# 01_MAIN.net
KiCad netlist of a schematic drawn in Altium Designer
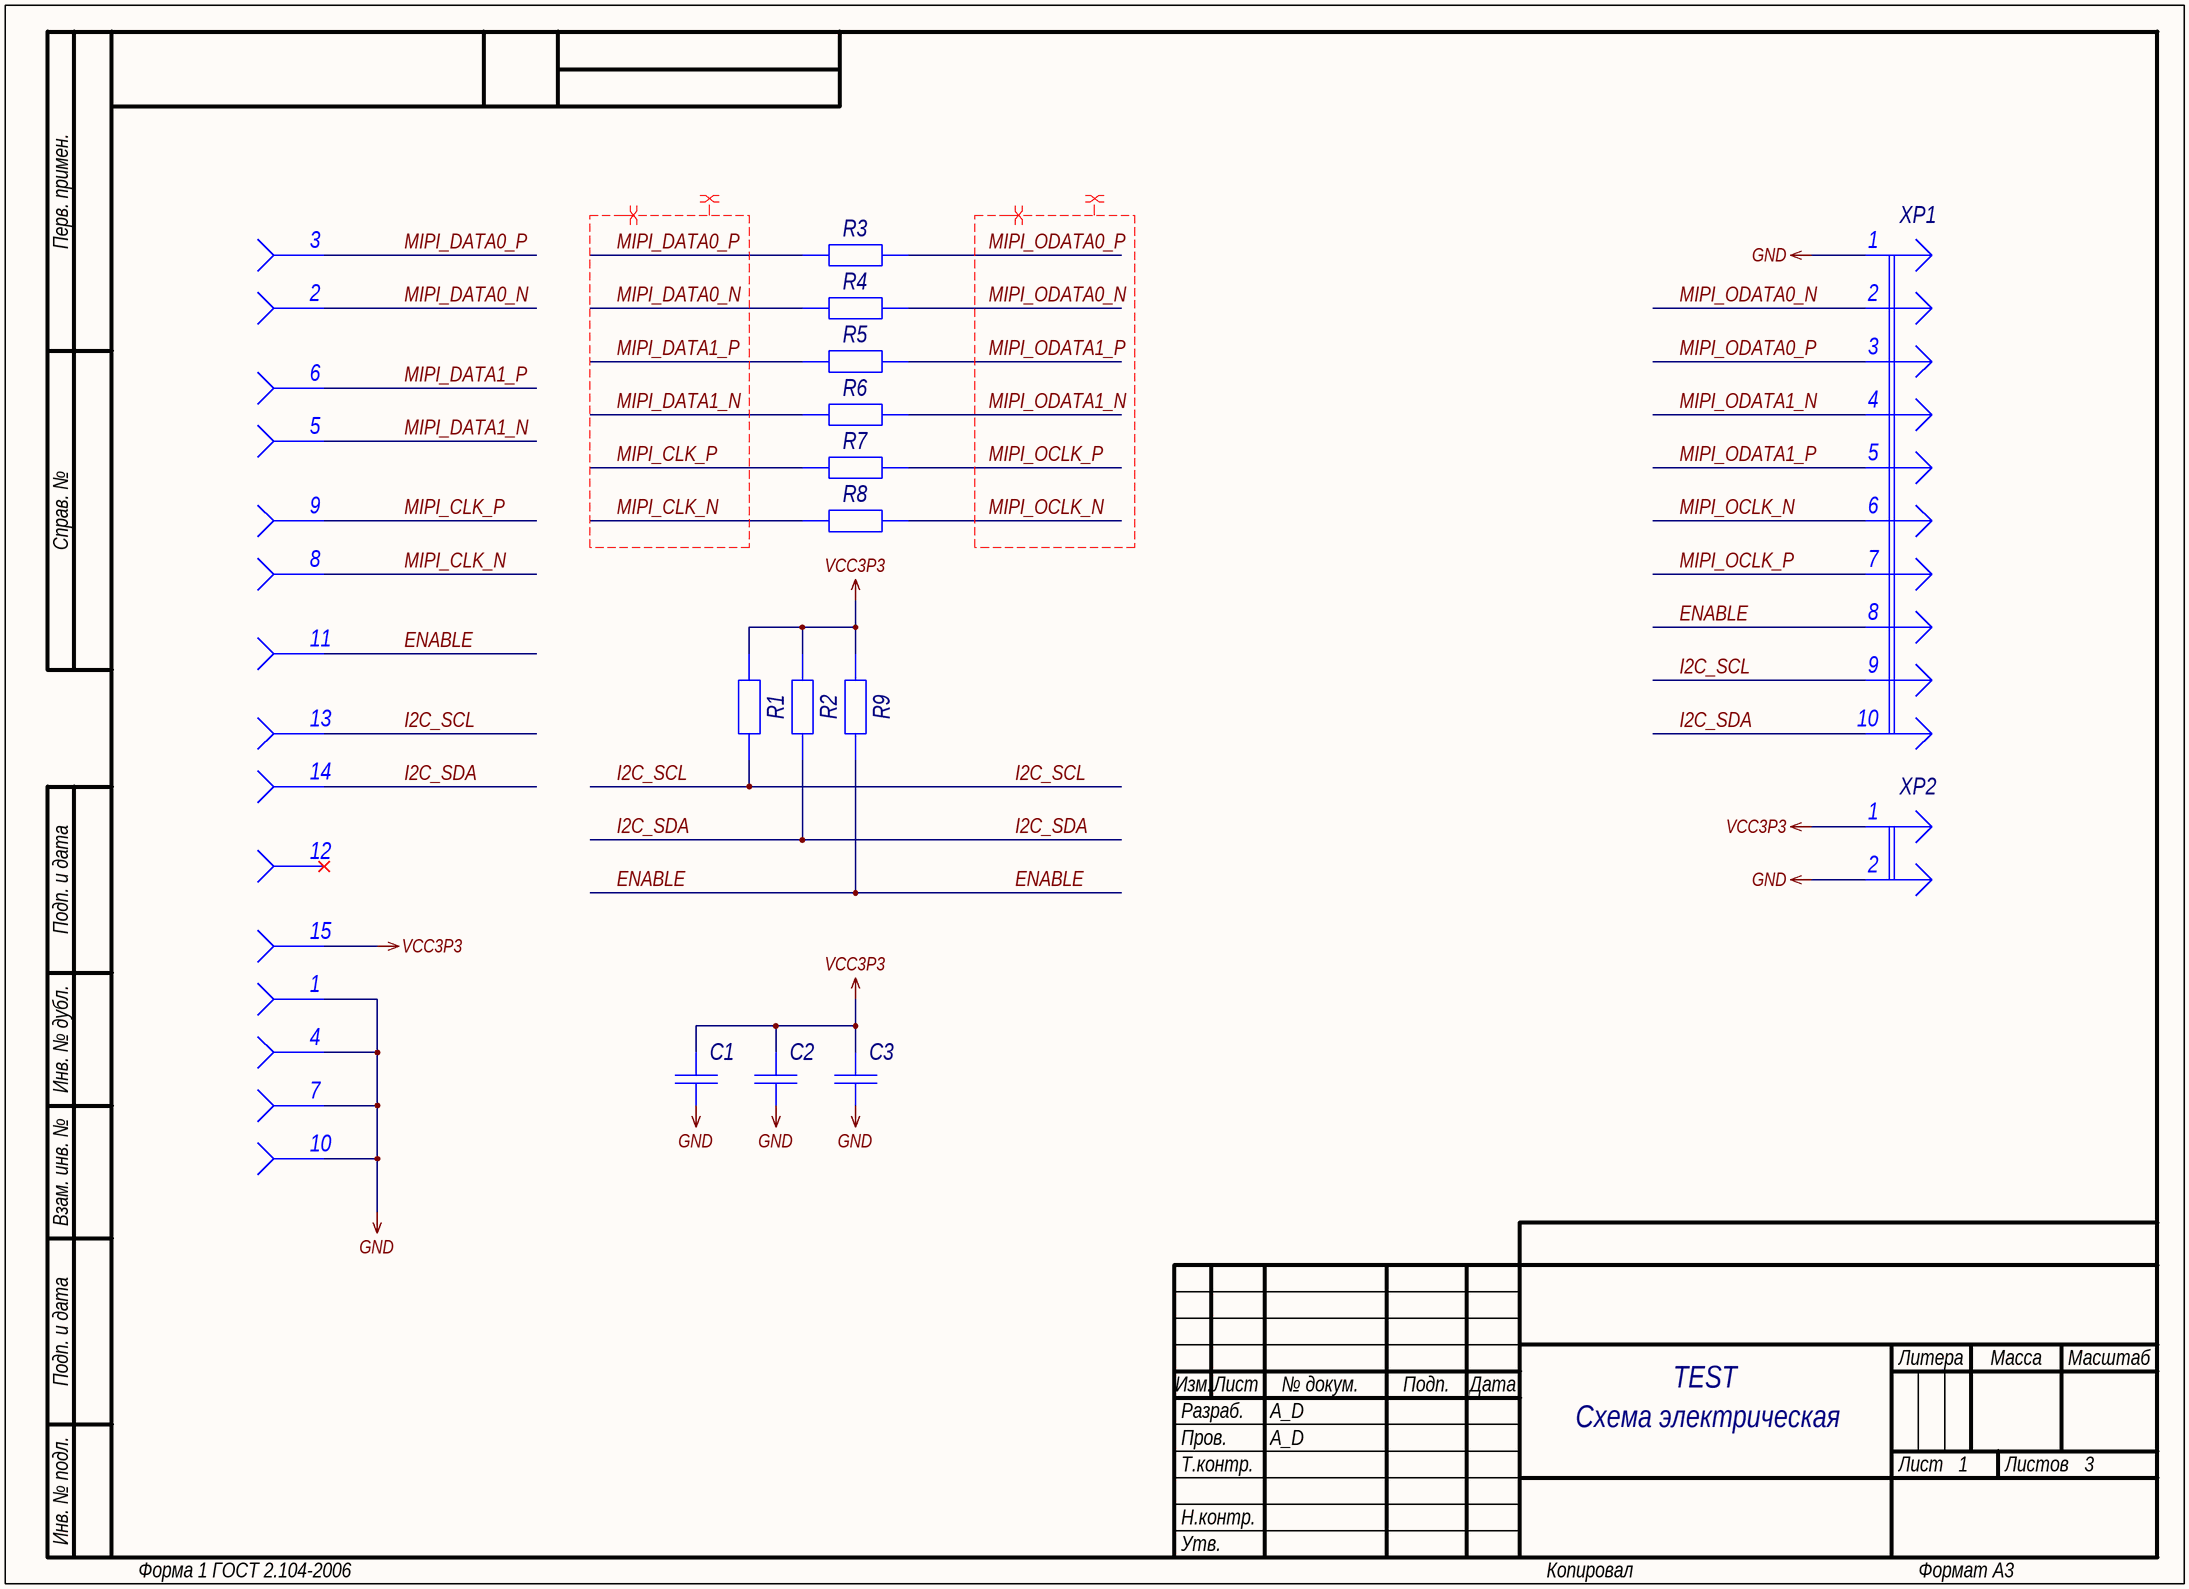
[diagram p0: 01_MAIN.SchDoc]

(export (version "E")
  (design (tool "Eeschema 10.0.6"))
  (components
    (comp (ref "C1")
      (value "Capacitor")
      (footprint "C0603_L")
      (fields
        (field (name "PART NUMBER") "GRM188R61A106KE69D")
        (field (name "VOLTAGE") "10V")
        (field (name "TOLERANCE") "±10%")
        (field (name "PUBLISHER") "Andrew Danich")
      )
      (libsource (lib "ADLib") (part "Capacitor"))
    )
    (comp (ref "C2")
      (value "Capacitor")
      (footprint "C0603_L")
      (fields
        (field (name "PART NUMBER") "GRM188R72A104KA35D")
        (field (name "VOLTAGE") "100V")
        (field (name "TOLERANCE") "±10%")
        (field (name "PUBLISHER") "Andrew Danich")
      )
      (libsource (lib "ADLib") (part "Capacitor"))
    )
    (comp (ref "C3")
      (value "Capacitor")
      (footprint "C0603_L")
      (fields
        (field (name "PART NUMBER") "GRM1885C2A102JA01D")
        (field (name "VOLTAGE") "100V")
        (field (name "TOLERANCE") "±5%")
        (field (name "PUBLISHER") "Andrew Danich")
      )
      (libsource (lib "ADLib") (part "Capacitor"))
    )
    (comp (ref "R1")
      (value "Resistor")
      (footprint "R0603_L")
      (fields
        (field (name "PART NUMBER") "RC0603JR-074K7L")
        (field (name "TOLERANCE") "±5%")
        (field (name "MANUFACTURER") "Yageo")
        (field (name "PUBLISHER") "Andrew Danich")
      )
      (libsource (lib "ADLib") (part "Resistor"))
    )
    (comp (ref "R2")
      (value "Resistor")
      (footprint "R0603_L")
      (fields
        (field (name "PART NUMBER") "RC0603JR-074K7L")
        (field (name "TOLERANCE") "±5%")
        (field (name "MANUFACTURER") "Yageo")
        (field (name "PUBLISHER") "Andrew Danich")
      )
      (libsource (lib "ADLib") (part "Resistor"))
    )
    (comp (ref "R3")
      (value "Resistor")
      (footprint "R0603_L")
      (fields
        (field (name "PART NUMBER") "RC0603JR-070R")
        (field (name "TOLERANCE") "±5%")
        (field (name "MANUFACTURER") "Yageo")
        (field (name "PUBLISHER") "Andrew Danich")
      )
      (libsource (lib "ADLib") (part "Resistor"))
    )
    (comp (ref "R4")
      (value "Resistor")
      (footprint "R0603_L")
      (fields
        (field (name "PART NUMBER") "RC0603JR-070R")
        (field (name "TOLERANCE") "±5%")
        (field (name "MANUFACTURER") "Yageo")
        (field (name "PUBLISHER") "Andrew Danich")
      )
      (libsource (lib "ADLib") (part "Resistor"))
    )
    (comp (ref "R5")
      (value "Resistor")
      (footprint "R0603_L")
      (fields
        (field (name "PART NUMBER") "RC0603JR-070R")
        (field (name "TOLERANCE") "±5%")
        (field (name "MANUFACTURER") "Yageo")
        (field (name "PUBLISHER") "Andrew Danich")
      )
      (libsource (lib "ADLib") (part "Resistor"))
    )
    (comp (ref "R6")
      (value "Resistor")
      (footprint "R0603_L")
      (fields
        (field (name "PART NUMBER") "RC0603JR-070R")
        (field (name "TOLERANCE") "±5%")
        (field (name "MANUFACTURER") "Yageo")
        (field (name "PUBLISHER") "Andrew Danich")
      )
      (libsource (lib "ADLib") (part "Resistor"))
    )
    (comp (ref "R7")
      (value "Resistor")
      (footprint "R0603_L")
      (fields
        (field (name "PART NUMBER") "RC0603JR-070R")
        (field (name "TOLERANCE") "±5%")
        (field (name "MANUFACTURER") "Yageo")
        (field (name "PUBLISHER") "Andrew Danich")
      )
      (libsource (lib "ADLib") (part "Resistor"))
    )
    (comp (ref "R8")
      (value "Resistor")
      (footprint "R0603_L")
      (fields
        (field (name "PART NUMBER") "RC0603JR-070R")
        (field (name "TOLERANCE") "±5%")
        (field (name "MANUFACTURER") "Yageo")
        (field (name "PUBLISHER") "Andrew Danich")
      )
      (libsource (lib "ADLib") (part "Resistor"))
    )
    (comp (ref "R9")
      (value "Resistor")
      (footprint "R0603_L")
      (fields
        (field (name "PART NUMBER") "RC0603JR-074K7L")
        (field (name "TOLERANCE") "±5%")
        (field (name "MANUFACTURER") "Yageo")
        (field (name "PUBLISHER") "Andrew Danich")
      )
      (libsource (lib "ADLib") (part "Resistor"))
    )
    (comp (ref "XP1")
      (value "Text")
      (footprint "PLS-10")
      (fields (field (name "PART NUMBER") "PLS-10") (field (name "PUBLISHER") "Andrew Danich"))
      (libsource (lib "ADLib") (part "Con-10-M"))
    )
    (comp (ref "XP2")
      (value "Text")
      (footprint "PLS-2")
      (fields (field (name "PART NUMBER") "PLS-2") (field (name "PUBLISHER") "Andrew Danich"))
      (libsource (lib "ADLib") (part "Con-2-M"))
    )
    (comp (ref "XS1")
      (value "CAM")
      (footprint "1-84953-5")
      (fields
        (field (name "PART NUMBER") "1-84953-5")
        (field (name "MANUFACTURER") "TE Connectivity")
        (field (name "PUBLISHER") "Andrew Danich")
      )
      (libsource (lib "ADLib") (part "Con-15-F_S"))
    )
  )
  (nets
    (net (code "1") (name "/ENABLE") (class "Default")
      (node (ref "R9") (pin "1") (pinfunction "1_1") (pintype "passive"))
      (node (ref "XP1") (pin "8") (pintype "passive"))
      (node (ref "XS1") (pin "11") (pintype "passive"))
    )
    (net (code "2") (name "/I2C_SCL") (class "Default")
      (node (ref "R1") (pin "1") (pinfunction "1_1") (pintype "passive"))
      (node (ref "XP1") (pin "9") (pintype "passive"))
      (node (ref "XS1") (pin "13") (pintype "passive"))
    )
    (net (code "3") (name "/I2C_SDA") (class "Default")
      (node (ref "R2") (pin "1") (pinfunction "1_1") (pintype "passive"))
      (node (ref "XP1") (pin "10") (pintype "passive"))
      (node (ref "XS1") (pin "14") (pintype "passive"))
    )
    (net (code "4") (name "/MIPI_CLK_N") (class "Default")
      (node (ref "R8") (pin "1") (pinfunction "1_1") (pintype "passive"))
      (node (ref "XS1") (pin "8") (pintype "passive"))
    )
    (net (code "5") (name "/MIPI_CLK_P") (class "Default")
      (node (ref "R7") (pin "1") (pinfunction "1_1") (pintype "passive"))
      (node (ref "XS1") (pin "9") (pintype "passive"))
    )
    (net (code "6") (name "/MIPI_DATA0_N") (class "Default")
      (node (ref "R4") (pin "1") (pinfunction "1_1") (pintype "passive"))
      (node (ref "XS1") (pin "2") (pintype "passive"))
    )
    (net (code "7") (name "/MIPI_DATA0_P") (class "Default")
      (node (ref "R3") (pin "1") (pinfunction "1_1") (pintype "passive"))
      (node (ref "XS1") (pin "3") (pintype "passive"))
    )
    (net (code "8") (name "/MIPI_DATA1_N") (class "Default")
      (node (ref "R6") (pin "1") (pinfunction "1_1") (pintype "passive"))
      (node (ref "XS1") (pin "5") (pintype "passive"))
    )
    (net (code "9") (name "/MIPI_DATA1_P") (class "Default")
      (node (ref "R5") (pin "1") (pinfunction "1_1") (pintype "passive"))
      (node (ref "XS1") (pin "6") (pintype "passive"))
    )
    (net (code "10") (name "/MIPI_OCLK_N") (class "Default")
      (node (ref "R8") (pin "2") (pinfunction "2_2") (pintype "passive"))
      (node (ref "XP1") (pin "6") (pintype "passive"))
    )
    (net (code "11") (name "/MIPI_OCLK_P") (class "Default")
      (node (ref "R7") (pin "2") (pinfunction "2_2") (pintype "passive"))
      (node (ref "XP1") (pin "7") (pintype "passive"))
    )
    (net (code "12") (name "/MIPI_ODATA0_N") (class "Default")
      (node (ref "R4") (pin "2") (pinfunction "2_2") (pintype "passive"))
      (node (ref "XP1") (pin "2") (pintype "passive"))
    )
    (net (code "13") (name "/MIPI_ODATA0_P") (class "Default")
      (node (ref "R3") (pin "2") (pinfunction "2_2") (pintype "passive"))
      (node (ref "XP1") (pin "3") (pintype "passive"))
    )
    (net (code "14") (name "/MIPI_ODATA1_N") (class "Default")
      (node (ref "R6") (pin "2") (pinfunction "2_2") (pintype "passive"))
      (node (ref "XP1") (pin "4") (pintype "passive"))
    )
    (net (code "15") (name "/MIPI_ODATA1_P") (class "Default")
      (node (ref "R5") (pin "2") (pinfunction "2_2") (pintype "passive"))
      (node (ref "XP1") (pin "5") (pintype "passive"))
    )
    (net (code "16") (name "GND") (class "Default")
      (node (ref "C1") (pin "1") (pinfunction "1_1") (pintype "passive"))
      (node (ref "C2") (pin "1") (pinfunction "1_1") (pintype "passive"))
      (node (ref "C3") (pin "1") (pinfunction "1_1") (pintype "passive"))
      (node (ref "XP1") (pin "1") (pintype "passive"))
      (node (ref "XP2") (pin "2") (pintype "passive"))
      (node (ref "XS1") (pin "1") (pintype "passive"))
      (node (ref "XS1") (pin "10") (pintype "passive"))
      (node (ref "XS1") (pin "4") (pintype "passive"))
      (node (ref "XS1") (pin "7") (pintype "passive"))
    )
    (net (code "17") (name "VCC3P3") (class "Default")
      (node (ref "C1") (pin "2") (pinfunction "2_2") (pintype "passive"))
      (node (ref "C2") (pin "2") (pinfunction "2_2") (pintype "passive"))
      (node (ref "C3") (pin "2") (pinfunction "2_2") (pintype "passive"))
      (node (ref "R1") (pin "2") (pinfunction "2_2") (pintype "passive"))
      (node (ref "R2") (pin "2") (pinfunction "2_2") (pintype "passive"))
      (node (ref "R9") (pin "2") (pinfunction "2_2") (pintype "passive"))
      (node (ref "XP2") (pin "1") (pintype "passive"))
      (node (ref "XS1") (pin "15") (pintype "passive"))
    )
    (net (code "18") (name "unconnected-(XS1-Pad12)") (class "Default")
      (node (ref "XS1") (pin "12") (pintype "passive+no_connect"))
    )
  )
)
